# S205C.net
KiCad netlist of a schematic drawn in EAGLE
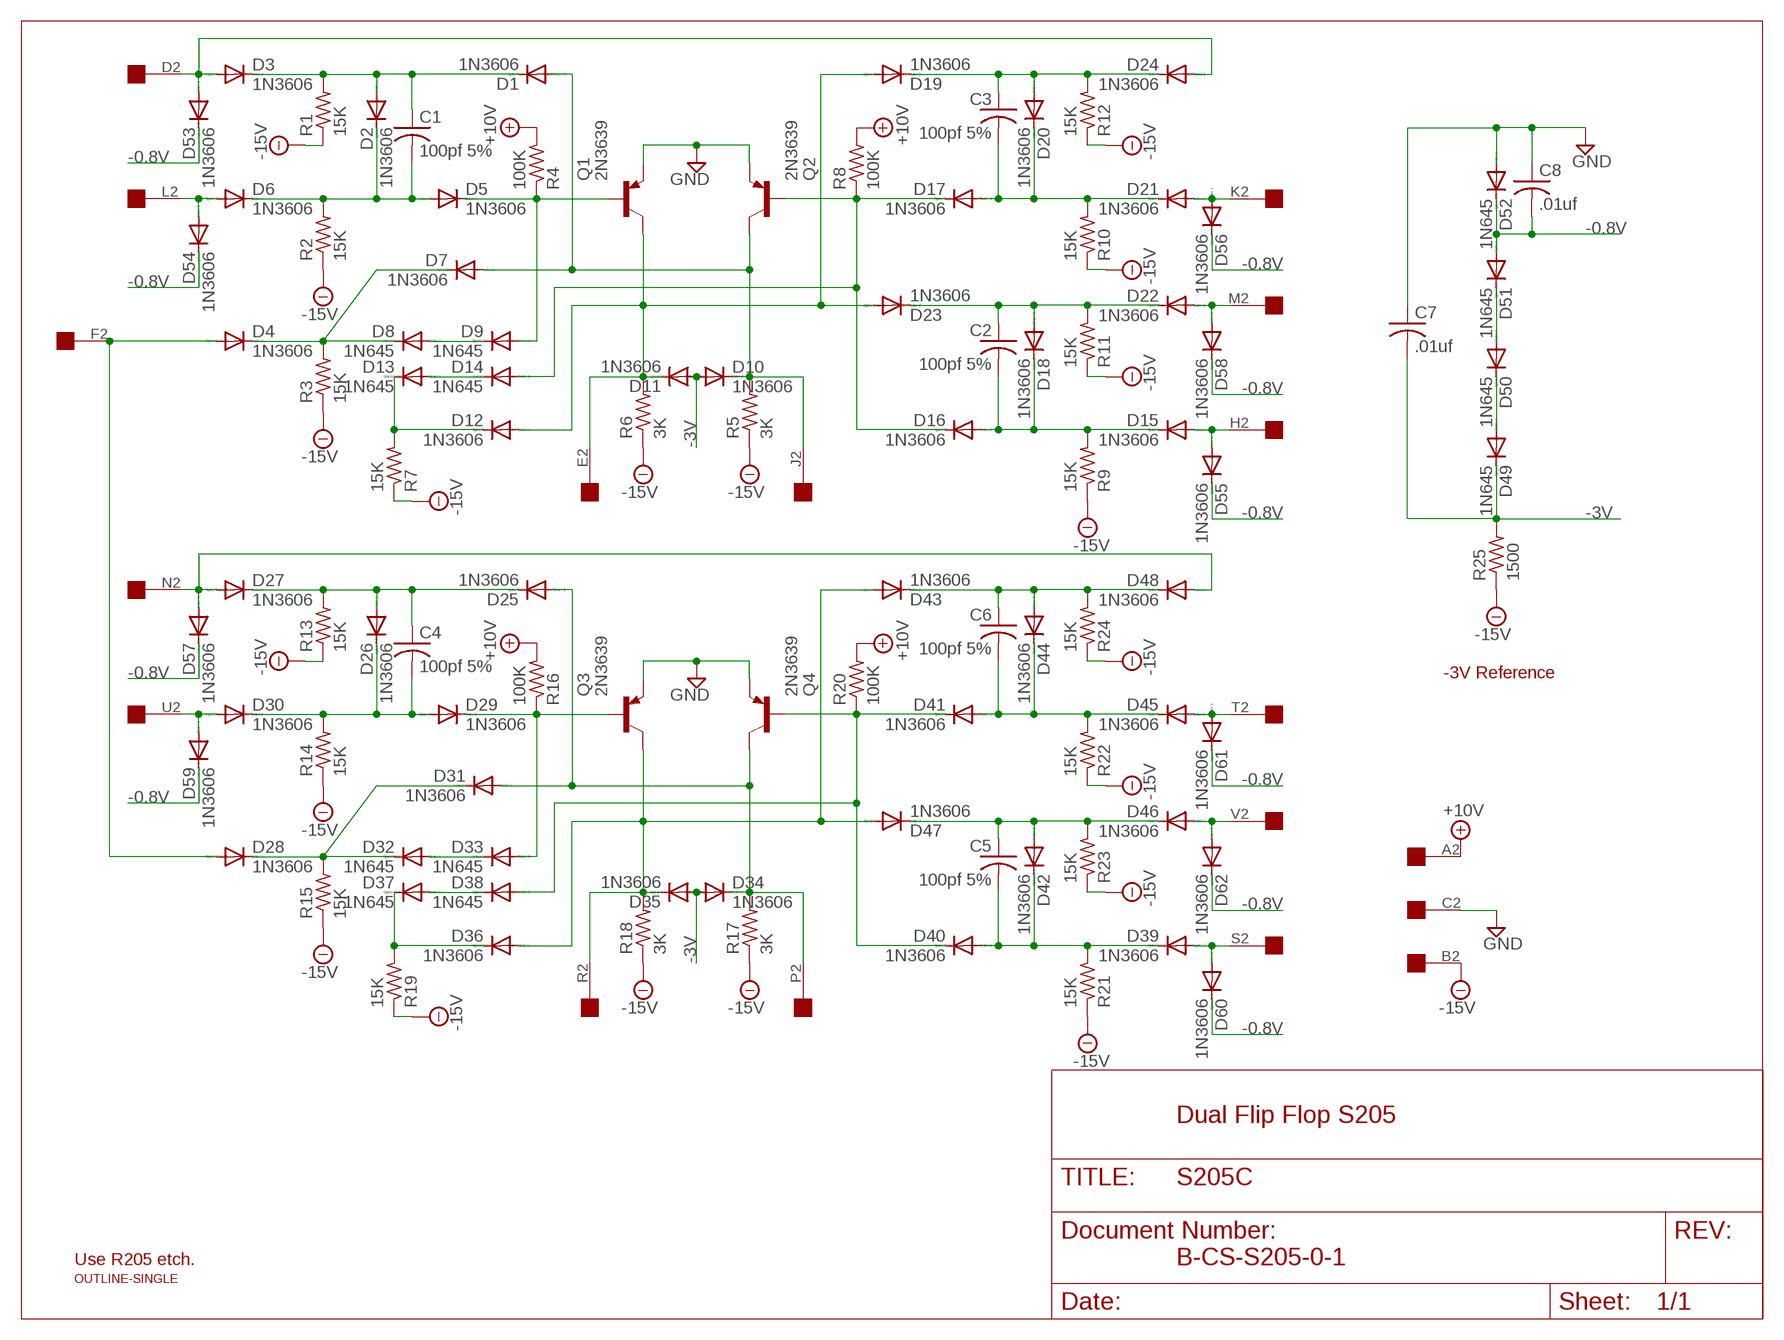
[diagram p0: schematic, sheet 1]

(export (version "E")
  (design (tool "Eeschema 10.0.6"))
  (components
    (comp (ref "C1")
      (value "100pf 5%")
      (footprint "eagle-import:C050-025X075")
      (libsource (lib "eagle-import") (part "C-US050-025X075"))
    )
    (comp (ref "C2")
      (value "100pf 5%")
      (footprint "eagle-import:C050-025X075")
      (libsource (lib "eagle-import") (part "C-US050-025X075"))
    )
    (comp (ref "C3")
      (value "100pf 5%")
      (footprint "eagle-import:C050-025X075")
      (libsource (lib "eagle-import") (part "C-US050-025X075"))
    )
    (comp (ref "C4")
      (value "100pf 5%")
      (footprint "eagle-import:C050-025X075")
      (libsource (lib "eagle-import") (part "C-US050-025X075"))
    )
    (comp (ref "C5")
      (value "100pf 5%")
      (footprint "eagle-import:C050-025X075")
      (libsource (lib "eagle-import") (part "C-US050-025X075"))
    )
    (comp (ref "C6")
      (value "100pf 5%")
      (footprint "eagle-import:C050-025X075")
      (libsource (lib "eagle-import") (part "C-US050-025X075"))
    )
    (comp (ref "C7")
      (value ".01uf")
      (footprint "eagle-import:C050-025X075")
      (libsource (lib "eagle-import") (part "C-US050-025X075"))
    )
    (comp (ref "C8")
      (value ".01uf")
      (footprint "eagle-import:C050-025X075")
      (libsource (lib "eagle-import") (part "C-US050-025X075"))
    )
    (comp (ref "D1")
      (value "1N3606")
      (footprint "eagle-import:DO35-10")
      (libsource (lib "eagle-import") (part "1N4148DO35-10"))
    )
    (comp (ref "D2")
      (value "1N3606")
      (footprint "eagle-import:DO35-10")
      (libsource (lib "eagle-import") (part "1N4148DO35-10"))
    )
    (comp (ref "D3")
      (value "1N3606")
      (footprint "eagle-import:DO35-10")
      (libsource (lib "eagle-import") (part "1N4148DO35-10"))
    )
    (comp (ref "D4")
      (value "1N3606")
      (footprint "eagle-import:DO35-10")
      (libsource (lib "eagle-import") (part "1N4148DO35-10"))
    )
    (comp (ref "D5")
      (value "1N3606")
      (footprint "eagle-import:DO35-10")
      (libsource (lib "eagle-import") (part "1N4148DO35-10"))
    )
    (comp (ref "D6")
      (value "1N3606")
      (footprint "eagle-import:DO35-10")
      (libsource (lib "eagle-import") (part "1N4148DO35-10"))
    )
    (comp (ref "D7")
      (value "1N3606")
      (footprint "eagle-import:DO35-10")
      (libsource (lib "eagle-import") (part "1N4148DO35-10"))
    )
    (comp (ref "D8")
      (value "1N645")
      (footprint "eagle-import:DO35-10")
      (libsource (lib "eagle-import") (part "1N4148DO35-10"))
    )
    (comp (ref "D9")
      (value "1N645")
      (footprint "eagle-import:DO35-10")
      (libsource (lib "eagle-import") (part "1N4148DO35-10"))
    )
    (comp (ref "D10")
      (value "1N3606")
      (footprint "eagle-import:DO35-10")
      (libsource (lib "eagle-import") (part "1N4148DO35-10"))
    )
    (comp (ref "D11")
      (value "1N3606")
      (footprint "eagle-import:DO35-10")
      (libsource (lib "eagle-import") (part "1N4148DO35-10"))
    )
    (comp (ref "D12")
      (value "1N3606")
      (footprint "eagle-import:DO35-10")
      (libsource (lib "eagle-import") (part "1N4148DO35-10"))
    )
    (comp (ref "D13")
      (value "1N645")
      (footprint "eagle-import:DO35-10")
      (libsource (lib "eagle-import") (part "1N4148DO35-10"))
    )
    (comp (ref "D14")
      (value "1N645")
      (footprint "eagle-import:DO35-10")
      (libsource (lib "eagle-import") (part "1N4148DO35-10"))
    )
    (comp (ref "D15")
      (value "1N3606")
      (footprint "eagle-import:DO35-10")
      (libsource (lib "eagle-import") (part "1N4148DO35-10"))
    )
    (comp (ref "D16")
      (value "1N3606")
      (footprint "eagle-import:DO35-10")
      (libsource (lib "eagle-import") (part "1N4148DO35-10"))
    )
    (comp (ref "D17")
      (value "1N3606")
      (footprint "eagle-import:DO35-10")
      (libsource (lib "eagle-import") (part "1N4148DO35-10"))
    )
    (comp (ref "D18")
      (value "1N3606")
      (footprint "eagle-import:DO35-10")
      (libsource (lib "eagle-import") (part "1N4148DO35-10"))
    )
    (comp (ref "D19")
      (value "1N3606")
      (footprint "eagle-import:DO35-10")
      (libsource (lib "eagle-import") (part "1N4148DO35-10"))
    )
    (comp (ref "D20")
      (value "1N3606")
      (footprint "eagle-import:DO35-10")
      (libsource (lib "eagle-import") (part "1N4148DO35-10"))
    )
    (comp (ref "D21")
      (value "1N3606")
      (footprint "eagle-import:DO35-10")
      (libsource (lib "eagle-import") (part "1N4148DO35-10"))
    )
    (comp (ref "D22")
      (value "1N3606")
      (footprint "eagle-import:DO35-10")
      (libsource (lib "eagle-import") (part "1N4148DO35-10"))
    )
    (comp (ref "D23")
      (value "1N3606")
      (footprint "eagle-import:DO35-10")
      (libsource (lib "eagle-import") (part "1N4148DO35-10"))
    )
    (comp (ref "D24")
      (value "1N3606")
      (footprint "eagle-import:DO35-10")
      (libsource (lib "eagle-import") (part "1N4148DO35-10"))
    )
    (comp (ref "D25")
      (value "1N3606")
      (footprint "eagle-import:DO35-10")
      (libsource (lib "eagle-import") (part "1N4148DO35-10"))
    )
    (comp (ref "D26")
      (value "1N3606")
      (footprint "eagle-import:DO35-10")
      (libsource (lib "eagle-import") (part "1N4148DO35-10"))
    )
    (comp (ref "D27")
      (value "1N3606")
      (footprint "eagle-import:DO35-10")
      (libsource (lib "eagle-import") (part "1N4148DO35-10"))
    )
    (comp (ref "D28")
      (value "1N3606")
      (footprint "eagle-import:DO35-10")
      (libsource (lib "eagle-import") (part "1N4148DO35-10"))
    )
    (comp (ref "D29")
      (value "1N3606")
      (footprint "eagle-import:DO35-10")
      (libsource (lib "eagle-import") (part "1N4148DO35-10"))
    )
    (comp (ref "D30")
      (value "1N3606")
      (footprint "eagle-import:DO35-10")
      (libsource (lib "eagle-import") (part "1N4148DO35-10"))
    )
    (comp (ref "D31")
      (value "1N3606")
      (footprint "eagle-import:DO35-10")
      (libsource (lib "eagle-import") (part "1N4148DO35-10"))
    )
    (comp (ref "D32")
      (value "1N645")
      (footprint "eagle-import:DO35-10")
      (libsource (lib "eagle-import") (part "1N4148DO35-10"))
    )
    (comp (ref "D33")
      (value "1N645")
      (footprint "eagle-import:DO35-10")
      (libsource (lib "eagle-import") (part "1N4148DO35-10"))
    )
    (comp (ref "D34")
      (value "1N3606")
      (footprint "eagle-import:DO35-10")
      (libsource (lib "eagle-import") (part "1N4148DO35-10"))
    )
    (comp (ref "D35")
      (value "1N3606")
      (footprint "eagle-import:DO35-10")
      (libsource (lib "eagle-import") (part "1N4148DO35-10"))
    )
    (comp (ref "D36")
      (value "1N3606")
      (footprint "eagle-import:DO35-10")
      (libsource (lib "eagle-import") (part "1N4148DO35-10"))
    )
    (comp (ref "D37")
      (value "1N645")
      (footprint "eagle-import:DO35-10")
      (libsource (lib "eagle-import") (part "1N4148DO35-10"))
    )
    (comp (ref "D38")
      (value "1N645")
      (footprint "eagle-import:DO35-10")
      (libsource (lib "eagle-import") (part "1N4148DO35-10"))
    )
    (comp (ref "D39")
      (value "1N3606")
      (footprint "eagle-import:DO35-10")
      (libsource (lib "eagle-import") (part "1N4148DO35-10"))
    )
    (comp (ref "D40")
      (value "1N3606")
      (footprint "eagle-import:DO35-10")
      (libsource (lib "eagle-import") (part "1N4148DO35-10"))
    )
    (comp (ref "D41")
      (value "1N3606")
      (footprint "eagle-import:DO35-10")
      (libsource (lib "eagle-import") (part "1N4148DO35-10"))
    )
    (comp (ref "D42")
      (value "1N3606")
      (footprint "eagle-import:DO35-10")
      (libsource (lib "eagle-import") (part "1N4148DO35-10"))
    )
    (comp (ref "D43")
      (value "1N3606")
      (footprint "eagle-import:DO35-10")
      (libsource (lib "eagle-import") (part "1N4148DO35-10"))
    )
    (comp (ref "D44")
      (value "1N3606")
      (footprint "eagle-import:DO35-10")
      (libsource (lib "eagle-import") (part "1N4148DO35-10"))
    )
    (comp (ref "D45")
      (value "1N3606")
      (footprint "eagle-import:DO35-10")
      (libsource (lib "eagle-import") (part "1N4148DO35-10"))
    )
    (comp (ref "D46")
      (value "1N3606")
      (footprint "eagle-import:DO35-10")
      (libsource (lib "eagle-import") (part "1N4148DO35-10"))
    )
    (comp (ref "D47")
      (value "1N3606")
      (footprint "eagle-import:DO35-10")
      (libsource (lib "eagle-import") (part "1N4148DO35-10"))
    )
    (comp (ref "D48")
      (value "1N3606")
      (footprint "eagle-import:DO35-10")
      (libsource (lib "eagle-import") (part "1N4148DO35-10"))
    )
    (comp (ref "D49")
      (value "1N645")
      (footprint "eagle-import:DO35-10")
      (libsource (lib "eagle-import") (part "1N4148DO35-10"))
    )
    (comp (ref "D50")
      (value "1N645")
      (footprint "eagle-import:DO35-10")
      (libsource (lib "eagle-import") (part "1N4148DO35-10"))
    )
    (comp (ref "D51")
      (value "1N645")
      (footprint "eagle-import:DO35-10")
      (libsource (lib "eagle-import") (part "1N4148DO35-10"))
    )
    (comp (ref "D52")
      (value "1N645")
      (footprint "eagle-import:DO35-10")
      (libsource (lib "eagle-import") (part "1N4148DO35-10"))
    )
    (comp (ref "D53")
      (value "1N3606")
      (footprint "eagle-import:DO35-10")
      (libsource (lib "eagle-import") (part "1N4148DO35-10"))
    )
    (comp (ref "D54")
      (value "1N3606")
      (footprint "eagle-import:DO35-10")
      (libsource (lib "eagle-import") (part "1N4148DO35-10"))
    )
    (comp (ref "D55")
      (value "1N3606")
      (footprint "eagle-import:DO35-10")
      (libsource (lib "eagle-import") (part "1N4148DO35-10"))
    )
    (comp (ref "D56")
      (value "1N3606")
      (footprint "eagle-import:DO35-10")
      (libsource (lib "eagle-import") (part "1N4148DO35-10"))
    )
    (comp (ref "D57")
      (value "1N3606")
      (footprint "eagle-import:DO35-10")
      (libsource (lib "eagle-import") (part "1N4148DO35-10"))
    )
    (comp (ref "D58")
      (value "1N3606")
      (footprint "eagle-import:DO35-10")
      (libsource (lib "eagle-import") (part "1N4148DO35-10"))
    )
    (comp (ref "D59")
      (value "1N3606")
      (footprint "eagle-import:DO35-10")
      (libsource (lib "eagle-import") (part "1N4148DO35-10"))
    )
    (comp (ref "D60")
      (value "1N3606")
      (footprint "eagle-import:DO35-10")
      (libsource (lib "eagle-import") (part "1N4148DO35-10"))
    )
    (comp (ref "D61")
      (value "1N3606")
      (footprint "eagle-import:DO35-10")
      (libsource (lib "eagle-import") (part "1N4148DO35-10"))
    )
    (comp (ref "D62")
      (value "1N3606")
      (footprint "eagle-import:DO35-10")
      (libsource (lib "eagle-import") (part "1N4148DO35-10"))
    )
    (comp (ref "Q1")
      (value "2N3639")
      (footprint "eagle-import:TO39")
      (libsource (lib "eagle-import") (part "2N3637"))
    )
    (comp (ref "Q2")
      (value "2N3639")
      (footprint "eagle-import:TO39")
      (libsource (lib "eagle-import") (part "2N3637"))
    )
    (comp (ref "Q3")
      (value "2N3639")
      (footprint "eagle-import:TO39")
      (libsource (lib "eagle-import") (part "2N3637"))
    )
    (comp (ref "Q4")
      (value "2N3639")
      (footprint "eagle-import:TO39")
      (libsource (lib "eagle-import") (part "2N3637"))
    )
    (comp (ref "R1")
      (value "15K")
      (footprint "eagle-import:0207_10")
      (libsource (lib "eagle-import") (part "R-US_0207/10"))
    )
    (comp (ref "R2")
      (value "15K")
      (footprint "eagle-import:0207_10")
      (libsource (lib "eagle-import") (part "R-US_0207/10"))
    )
    (comp (ref "R3")
      (value "15K")
      (footprint "eagle-import:0207_10")
      (libsource (lib "eagle-import") (part "R-US_0207/10"))
    )
    (comp (ref "R4")
      (value "100K")
      (footprint "eagle-import:0207_10")
      (libsource (lib "eagle-import") (part "R-US_0207/10"))
    )
    (comp (ref "R5")
      (value "3K")
      (footprint "eagle-import:0207_10")
      (libsource (lib "eagle-import") (part "R-US_0207/10"))
    )
    (comp (ref "R6")
      (value "3K")
      (footprint "eagle-import:0207_10")
      (libsource (lib "eagle-import") (part "R-US_0207/10"))
    )
    (comp (ref "R7")
      (value "15K")
      (footprint "eagle-import:0207_10")
      (libsource (lib "eagle-import") (part "R-US_0207/10"))
    )
    (comp (ref "R8")
      (value "100K")
      (footprint "eagle-import:0207_10")
      (libsource (lib "eagle-import") (part "R-US_0207/10"))
    )
    (comp (ref "R9")
      (value "15K")
      (footprint "eagle-import:0207_10")
      (libsource (lib "eagle-import") (part "R-US_0207/10"))
    )
    (comp (ref "R10")
      (value "15K")
      (footprint "eagle-import:0207_10")
      (libsource (lib "eagle-import") (part "R-US_0207/10"))
    )
    (comp (ref "R11")
      (value "15K")
      (footprint "eagle-import:0207_10")
      (libsource (lib "eagle-import") (part "R-US_0207/10"))
    )
    (comp (ref "R12")
      (value "15K")
      (footprint "eagle-import:0207_10")
      (libsource (lib "eagle-import") (part "R-US_0207/10"))
    )
    (comp (ref "R13")
      (value "15K")
      (footprint "eagle-import:0207_10")
      (libsource (lib "eagle-import") (part "R-US_0207/10"))
    )
    (comp (ref "R14")
      (value "15K")
      (footprint "eagle-import:0207_10")
      (libsource (lib "eagle-import") (part "R-US_0207/10"))
    )
    (comp (ref "R15")
      (value "15K")
      (footprint "eagle-import:0207_10")
      (libsource (lib "eagle-import") (part "R-US_0207/10"))
    )
    (comp (ref "R16")
      (value "100K")
      (footprint "eagle-import:0207_10")
      (libsource (lib "eagle-import") (part "R-US_0207/10"))
    )
    (comp (ref "R17")
      (value "3K")
      (footprint "eagle-import:0207_10")
      (libsource (lib "eagle-import") (part "R-US_0207/10"))
    )
    (comp (ref "R18")
      (value "3K")
      (footprint "eagle-import:0207_10")
      (libsource (lib "eagle-import") (part "R-US_0207/10"))
    )
    (comp (ref "R19")
      (value "15K")
      (footprint "eagle-import:0207_10")
      (libsource (lib "eagle-import") (part "R-US_0207/10"))
    )
    (comp (ref "R20")
      (value "100K")
      (footprint "eagle-import:0207_10")
      (libsource (lib "eagle-import") (part "R-US_0207/10"))
    )
    (comp (ref "R21")
      (value "15K")
      (footprint "eagle-import:0207_10")
      (libsource (lib "eagle-import") (part "R-US_0207/10"))
    )
    (comp (ref "R22")
      (value "15K")
      (footprint "eagle-import:0207_10")
      (libsource (lib "eagle-import") (part "R-US_0207/10"))
    )
    (comp (ref "R23")
      (value "15K")
      (footprint "eagle-import:0207_10")
      (libsource (lib "eagle-import") (part "R-US_0207/10"))
    )
    (comp (ref "R24")
      (value "15K")
      (footprint "eagle-import:0207_10")
      (libsource (lib "eagle-import") (part "R-US_0207/10"))
    )
    (comp (ref "R25")
      (value "1500")
      (footprint "eagle-import:0207_10")
      (libsource (lib "eagle-import") (part "R-US_0207/10"))
    )
    (comp (ref "U$1")
      (value "OUTLINE-SINGLE")
      (footprint "eagle-import:SINGLE")
      (libsource (lib "eagle-import") (part "OUTLINE-SINGLE"))
    )
    (comp (ref "U$2")
      (value "EDGE-1")
      (footprint "eagle-import:EDGE-CON1")
      (libsource (lib "eagle-import") (part "EDGE-1"))
    )
  )
  (nets
    (net (code "1") (name "+10V") (class "Default")
      (node (ref "R16") (pin "2") (pinfunction "2_2") (pintype "passive"))
      (node (ref "R20") (pin "2") (pinfunction "2_2") (pintype "passive"))
      (node (ref "R4") (pin "2") (pinfunction "2_2") (pintype "passive"))
      (node (ref "R8") (pin "2") (pinfunction "2_2") (pintype "passive"))
      (node (ref "U$2") (pin "A2") (pinfunction "1_A2") (pintype "bidirectional"))
    )
    (net (code "2") (name "-15V") (class "Default")
      (node (ref "R1") (pin "1") (pinfunction "1_1") (pintype "passive"))
      (node (ref "R10") (pin "1") (pinfunction "1_1") (pintype "passive"))
      (node (ref "R11") (pin "1") (pinfunction "1_1") (pintype "passive"))
      (node (ref "R12") (pin "1") (pinfunction "1_1") (pintype "passive"))
      (node (ref "R13") (pin "1") (pinfunction "1_1") (pintype "passive"))
      (node (ref "R14") (pin "1") (pinfunction "1_1") (pintype "passive"))
      (node (ref "R15") (pin "1") (pinfunction "1_1") (pintype "passive"))
      (node (ref "R17") (pin "1") (pinfunction "1_1") (pintype "passive"))
      (node (ref "R18") (pin "1") (pinfunction "1_1") (pintype "passive"))
      (node (ref "R19") (pin "1") (pinfunction "1_1") (pintype "passive"))
      (node (ref "R2") (pin "1") (pinfunction "1_1") (pintype "passive"))
      (node (ref "R21") (pin "1") (pinfunction "1_1") (pintype "passive"))
      (node (ref "R22") (pin "1") (pinfunction "1_1") (pintype "passive"))
      (node (ref "R23") (pin "1") (pinfunction "1_1") (pintype "passive"))
      (node (ref "R24") (pin "1") (pinfunction "1_1") (pintype "passive"))
      (node (ref "R25") (pin "1") (pinfunction "1_1") (pintype "passive"))
      (node (ref "R3") (pin "1") (pinfunction "1_1") (pintype "passive"))
      (node (ref "R5") (pin "1") (pinfunction "1_1") (pintype "passive"))
      (node (ref "R6") (pin "1") (pinfunction "1_1") (pintype "passive"))
      (node (ref "R7") (pin "1") (pinfunction "1_1") (pintype "passive"))
      (node (ref "R9") (pin "1") (pinfunction "1_1") (pintype "passive"))
      (node (ref "U$2") (pin "B2") (pinfunction "1_B2") (pintype "bidirectional"))
    )
    (net (code "3") (name "/-0.8V") (class "Default")
      (node (ref "C8") (pin "2") (pinfunction "2_2") (pintype "passive"))
      (node (ref "D51") (pin "A") (pinfunction "A_A") (pintype "passive"))
      (node (ref "D52") (pin "C") (pinfunction "C_C") (pintype "passive"))
      (node (ref "D53") (pin "C") (pinfunction "C_C") (pintype "passive"))
      (node (ref "D54") (pin "C") (pinfunction "C_C") (pintype "passive"))
      (node (ref "D55") (pin "C") (pinfunction "C_C") (pintype "passive"))
      (node (ref "D56") (pin "C") (pinfunction "C_C") (pintype "passive"))
      (node (ref "D57") (pin "C") (pinfunction "C_C") (pintype "passive"))
      (node (ref "D58") (pin "C") (pinfunction "C_C") (pintype "passive"))
      (node (ref "D59") (pin "C") (pinfunction "C_C") (pintype "passive"))
      (node (ref "D60") (pin "C") (pinfunction "C_C") (pintype "passive"))
      (node (ref "D61") (pin "C") (pinfunction "C_C") (pintype "passive"))
      (node (ref "D62") (pin "C") (pinfunction "C_C") (pintype "passive"))
    )
    (net (code "4") (name "/-3V") (class "Default")
      (node (ref "C7") (pin "2") (pinfunction "2_2") (pintype "passive"))
      (node (ref "D10") (pin "A") (pinfunction "A_A") (pintype "passive"))
      (node (ref "D11") (pin "A") (pinfunction "A_A") (pintype "passive"))
      (node (ref "D34") (pin "A") (pinfunction "A_A") (pintype "passive"))
      (node (ref "D35") (pin "A") (pinfunction "A_A") (pintype "passive"))
      (node (ref "D49") (pin "C") (pinfunction "C_C") (pintype "passive"))
      (node (ref "R25") (pin "2") (pinfunction "2_2") (pintype "passive"))
    )
    (net (code "5") (name "GND") (class "Default")
      (node (ref "C7") (pin "1") (pinfunction "1_1") (pintype "passive"))
      (node (ref "C8") (pin "1") (pinfunction "1_1") (pintype "passive"))
      (node (ref "D52") (pin "A") (pinfunction "A_A") (pintype "passive"))
      (node (ref "Q1") (pin "1") (pinfunction "E_1") (pintype "passive"))
      (node (ref "Q2") (pin "1") (pinfunction "E_1") (pintype "passive"))
      (node (ref "Q3") (pin "1") (pinfunction "E_1") (pintype "passive"))
      (node (ref "Q4") (pin "1") (pinfunction "E_1") (pintype "passive"))
      (node (ref "U$2") (pin "C2") (pinfunction "1_C2") (pintype "bidirectional"))
    )
    (net (code "6") (name "Net-(C1-Pad1)") (class "Default")
      (node (ref "C1") (pin "1") (pinfunction "1_1") (pintype "passive"))
      (node (ref "D1") (pin "C") (pinfunction "C_C") (pintype "passive"))
      (node (ref "D2") (pin "A") (pinfunction "A_A") (pintype "passive"))
      (node (ref "D3") (pin "C") (pinfunction "C_C") (pintype "passive"))
      (node (ref "R1") (pin "2") (pinfunction "2_2") (pintype "passive"))
    )
    (net (code "7") (name "Net-(C1-Pad2)") (class "Default")
      (node (ref "C1") (pin "2") (pinfunction "2_2") (pintype "passive"))
      (node (ref "D2") (pin "C") (pinfunction "C_C") (pintype "passive"))
      (node (ref "D5") (pin "A") (pinfunction "A_A") (pintype "passive"))
      (node (ref "D6") (pin "C") (pinfunction "C_C") (pintype "passive"))
      (node (ref "R2") (pin "2") (pinfunction "2_2") (pintype "passive"))
    )
    (net (code "8") (name "Net-(C2-Pad1)") (class "Default")
      (node (ref "C2") (pin "1") (pinfunction "1_1") (pintype "passive"))
      (node (ref "D18") (pin "A") (pinfunction "A_A") (pintype "passive"))
      (node (ref "D22") (pin "C") (pinfunction "C_C") (pintype "passive"))
      (node (ref "D23") (pin "C") (pinfunction "C_C") (pintype "passive"))
      (node (ref "R11") (pin "2") (pinfunction "2_2") (pintype "passive"))
    )
    (net (code "9") (name "Net-(C2-Pad2)") (class "Default")
      (node (ref "C2") (pin "2") (pinfunction "2_2") (pintype "passive"))
      (node (ref "D15") (pin "C") (pinfunction "C_C") (pintype "passive"))
      (node (ref "D16") (pin "A") (pinfunction "A_A") (pintype "passive"))
      (node (ref "D18") (pin "C") (pinfunction "C_C") (pintype "passive"))
      (node (ref "R9") (pin "2") (pinfunction "2_2") (pintype "passive"))
    )
    (net (code "10") (name "Net-(C3-Pad1)") (class "Default")
      (node (ref "C3") (pin "1") (pinfunction "1_1") (pintype "passive"))
      (node (ref "D19") (pin "C") (pinfunction "C_C") (pintype "passive"))
      (node (ref "D20") (pin "A") (pinfunction "A_A") (pintype "passive"))
      (node (ref "D24") (pin "C") (pinfunction "C_C") (pintype "passive"))
      (node (ref "R12") (pin "2") (pinfunction "2_2") (pintype "passive"))
    )
    (net (code "11") (name "Net-(C3-Pad2)") (class "Default")
      (node (ref "C3") (pin "2") (pinfunction "2_2") (pintype "passive"))
      (node (ref "D17") (pin "A") (pinfunction "A_A") (pintype "passive"))
      (node (ref "D20") (pin "C") (pinfunction "C_C") (pintype "passive"))
      (node (ref "D21") (pin "C") (pinfunction "C_C") (pintype "passive"))
      (node (ref "R10") (pin "2") (pinfunction "2_2") (pintype "passive"))
    )
    (net (code "12") (name "Net-(C4-Pad1)") (class "Default")
      (node (ref "C4") (pin "1") (pinfunction "1_1") (pintype "passive"))
      (node (ref "D25") (pin "C") (pinfunction "C_C") (pintype "passive"))
      (node (ref "D26") (pin "A") (pinfunction "A_A") (pintype "passive"))
      (node (ref "D27") (pin "C") (pinfunction "C_C") (pintype "passive"))
      (node (ref "R13") (pin "2") (pinfunction "2_2") (pintype "passive"))
    )
    (net (code "13") (name "Net-(C4-Pad2)") (class "Default")
      (node (ref "C4") (pin "2") (pinfunction "2_2") (pintype "passive"))
      (node (ref "D26") (pin "C") (pinfunction "C_C") (pintype "passive"))
      (node (ref "D29") (pin "A") (pinfunction "A_A") (pintype "passive"))
      (node (ref "D30") (pin "C") (pinfunction "C_C") (pintype "passive"))
      (node (ref "R14") (pin "2") (pinfunction "2_2") (pintype "passive"))
    )
    (net (code "14") (name "Net-(C5-Pad1)") (class "Default")
      (node (ref "C5") (pin "1") (pinfunction "1_1") (pintype "passive"))
      (node (ref "D42") (pin "A") (pinfunction "A_A") (pintype "passive"))
      (node (ref "D46") (pin "C") (pinfunction "C_C") (pintype "passive"))
      (node (ref "D47") (pin "C") (pinfunction "C_C") (pintype "passive"))
      (node (ref "R23") (pin "2") (pinfunction "2_2") (pintype "passive"))
    )
    (net (code "15") (name "Net-(C5-Pad2)") (class "Default")
      (node (ref "C5") (pin "2") (pinfunction "2_2") (pintype "passive"))
      (node (ref "D39") (pin "C") (pinfunction "C_C") (pintype "passive"))
      (node (ref "D40") (pin "A") (pinfunction "A_A") (pintype "passive"))
      (node (ref "D42") (pin "C") (pinfunction "C_C") (pintype "passive"))
      (node (ref "R21") (pin "2") (pinfunction "2_2") (pintype "passive"))
    )
    (net (code "16") (name "Net-(C6-Pad1)") (class "Default")
      (node (ref "C6") (pin "1") (pinfunction "1_1") (pintype "passive"))
      (node (ref "D43") (pin "C") (pinfunction "C_C") (pintype "passive"))
      (node (ref "D44") (pin "A") (pinfunction "A_A") (pintype "passive"))
      (node (ref "D48") (pin "C") (pinfunction "C_C") (pintype "passive"))
      (node (ref "R24") (pin "2") (pinfunction "2_2") (pintype "passive"))
    )
    (net (code "17") (name "Net-(C6-Pad2)") (class "Default")
      (node (ref "C6") (pin "2") (pinfunction "2_2") (pintype "passive"))
      (node (ref "D41") (pin "A") (pinfunction "A_A") (pintype "passive"))
      (node (ref "D44") (pin "C") (pinfunction "C_C") (pintype "passive"))
      (node (ref "D45") (pin "C") (pinfunction "C_C") (pintype "passive"))
      (node (ref "R22") (pin "2") (pinfunction "2_2") (pintype "passive"))
    )
    (net (code "18") (name "Net-(D4-PadC)") (class "Default")
      (node (ref "D4") (pin "C") (pinfunction "C_C") (pintype "passive"))
      (node (ref "D7") (pin "C") (pinfunction "C_C") (pintype "passive"))
      (node (ref "D8") (pin "C") (pinfunction "C_C") (pintype "passive"))
      (node (ref "R3") (pin "2") (pinfunction "2_2") (pintype "passive"))
    )
    (net (code "19") (name "Net-(D8-PadA)") (class "Default")
      (node (ref "D8") (pin "A") (pinfunction "A_A") (pintype "passive"))
      (node (ref "D9") (pin "C") (pinfunction "C_C") (pintype "passive"))
    )
    (net (code "20") (name "Net-(D12-PadC)") (class "Default")
      (node (ref "D12") (pin "C") (pinfunction "C_C") (pintype "passive"))
      (node (ref "D13") (pin "C") (pinfunction "C_C") (pintype "passive"))
      (node (ref "R7") (pin "2") (pinfunction "2_2") (pintype "passive"))
    )
    (net (code "21") (name "Net-(D13-PadA)") (class "Default")
      (node (ref "D13") (pin "A") (pinfunction "A_A") (pintype "passive"))
      (node (ref "D14") (pin "C") (pinfunction "C_C") (pintype "passive"))
    )
    (net (code "22") (name "Net-(D28-PadC)") (class "Default")
      (node (ref "D28") (pin "C") (pinfunction "C_C") (pintype "passive"))
      (node (ref "D31") (pin "C") (pinfunction "C_C") (pintype "passive"))
      (node (ref "D32") (pin "C") (pinfunction "C_C") (pintype "passive"))
      (node (ref "R15") (pin "2") (pinfunction "2_2") (pintype "passive"))
    )
    (net (code "23") (name "Net-(D32-PadA)") (class "Default")
      (node (ref "D32") (pin "A") (pinfunction "A_A") (pintype "passive"))
      (node (ref "D33") (pin "C") (pinfunction "C_C") (pintype "passive"))
    )
    (net (code "24") (name "Net-(D36-PadC)") (class "Default")
      (node (ref "D36") (pin "C") (pinfunction "C_C") (pintype "passive"))
      (node (ref "D37") (pin "C") (pinfunction "C_C") (pintype "passive"))
      (node (ref "R19") (pin "2") (pinfunction "2_2") (pintype "passive"))
    )
    (net (code "25") (name "Net-(D37-PadA)") (class "Default")
      (node (ref "D37") (pin "A") (pinfunction "A_A") (pintype "passive"))
      (node (ref "D38") (pin "C") (pinfunction "C_C") (pintype "passive"))
    )
    (net (code "26") (name "Net-(D49-PadA)") (class "Default")
      (node (ref "D49") (pin "A") (pinfunction "A_A") (pintype "passive"))
      (node (ref "D50") (pin "C") (pinfunction "C_C") (pintype "passive"))
    )
    (net (code "27") (name "Net-(D50-PadA)") (class "Default")
      (node (ref "D50") (pin "A") (pinfunction "A_A") (pintype "passive"))
      (node (ref "D51") (pin "C") (pinfunction "C_C") (pintype "passive"))
    )
    (net (code "28") (name "Net-(Q1-B)") (class "Default")
      (node (ref "D5") (pin "C") (pinfunction "C_C") (pintype "passive"))
      (node (ref "D9") (pin "A") (pinfunction "A_A") (pintype "passive"))
      (node (ref "Q1") (pin "2") (pinfunction "B_2") (pintype "passive"))
      (node (ref "R4") (pin "1") (pinfunction "1_1") (pintype "passive"))
    )
    (net (code "29") (name "Net-(Q1-C)") (class "Default")
      (node (ref "D11") (pin "C") (pinfunction "C_C") (pintype "passive"))
      (node (ref "D12") (pin "A") (pinfunction "A_A") (pintype "passive"))
      (node (ref "D19") (pin "A") (pinfunction "A_A") (pintype "passive"))
      (node (ref "D23") (pin "A") (pinfunction "A_A") (pintype "passive"))
      (node (ref "Q1") (pin "3") (pinfunction "C_3") (pintype "passive"))
      (node (ref "R6") (pin "2") (pinfunction "2_2") (pintype "passive"))
      (node (ref "U$2") (pin "E2") (pinfunction "1_E2") (pintype "bidirectional"))
    )
    (net (code "30") (name "Net-(Q2-B)") (class "Default")
      (node (ref "D14") (pin "A") (pinfunction "A_A") (pintype "passive"))
      (node (ref "D16") (pin "C") (pinfunction "C_C") (pintype "passive"))
      (node (ref "D17") (pin "C") (pinfunction "C_C") (pintype "passive"))
      (node (ref "Q2") (pin "2") (pinfunction "B_2") (pintype "passive"))
      (node (ref "R8") (pin "1") (pinfunction "1_1") (pintype "passive"))
    )
    (net (code "31") (name "Net-(Q2-C)") (class "Default")
      (node (ref "D1") (pin "A") (pinfunction "A_A") (pintype "passive"))
      (node (ref "D10") (pin "C") (pinfunction "C_C") (pintype "passive"))
      (node (ref "D7") (pin "A") (pinfunction "A_A") (pintype "passive"))
      (node (ref "Q2") (pin "3") (pinfunction "C_3") (pintype "passive"))
      (node (ref "R5") (pin "2") (pinfunction "2_2") (pintype "passive"))
      (node (ref "U$2") (pin "J2") (pinfunction "1_J2") (pintype "bidirectional"))
    )
    (net (code "32") (name "Net-(Q3-B)") (class "Default")
      (node (ref "D29") (pin "C") (pinfunction "C_C") (pintype "passive"))
      (node (ref "D33") (pin "A") (pinfunction "A_A") (pintype "passive"))
      (node (ref "Q3") (pin "2") (pinfunction "B_2") (pintype "passive"))
      (node (ref "R16") (pin "1") (pinfunction "1_1") (pintype "passive"))
    )
    (net (code "33") (name "Net-(Q3-C)") (class "Default")
      (node (ref "D35") (pin "C") (pinfunction "C_C") (pintype "passive"))
      (node (ref "D36") (pin "A") (pinfunction "A_A") (pintype "passive"))
      (node (ref "D43") (pin "A") (pinfunction "A_A") (pintype "passive"))
      (node (ref "D47") (pin "A") (pinfunction "A_A") (pintype "passive"))
      (node (ref "Q3") (pin "3") (pinfunction "C_3") (pintype "passive"))
      (node (ref "R18") (pin "2") (pinfunction "2_2") (pintype "passive"))
      (node (ref "U$2") (pin "R2") (pinfunction "1_R2") (pintype "bidirectional"))
    )
    (net (code "34") (name "Net-(Q4-B)") (class "Default")
      (node (ref "D38") (pin "A") (pinfunction "A_A") (pintype "passive"))
      (node (ref "D40") (pin "C") (pinfunction "C_C") (pintype "passive"))
      (node (ref "D41") (pin "C") (pinfunction "C_C") (pintype "passive"))
      (node (ref "Q4") (pin "2") (pinfunction "B_2") (pintype "passive"))
      (node (ref "R20") (pin "1") (pinfunction "1_1") (pintype "passive"))
    )
    (net (code "35") (name "Net-(Q4-C)") (class "Default")
      (node (ref "D25") (pin "A") (pinfunction "A_A") (pintype "passive"))
      (node (ref "D31") (pin "A") (pinfunction "A_A") (pintype "passive"))
      (node (ref "D34") (pin "C") (pinfunction "C_C") (pintype "passive"))
      (node (ref "Q4") (pin "3") (pinfunction "C_3") (pintype "passive"))
      (node (ref "R17") (pin "2") (pinfunction "2_2") (pintype "passive"))
      (node (ref "U$2") (pin "P2") (pinfunction "1_P2") (pintype "bidirectional"))
    )
    (net (code "36") (name "Net-(U$2D-1)") (class "Default")
      (node (ref "D24") (pin "A") (pinfunction "A_A") (pintype "passive"))
      (node (ref "D3") (pin "A") (pinfunction "A_A") (pintype "passive"))
      (node (ref "D53") (pin "A") (pinfunction "A_A") (pintype "passive"))
      (node (ref "U$2") (pin "D2") (pinfunction "1_D2") (pintype "bidirectional"))
    )
    (net (code "37") (name "Net-(U$2F-1)") (class "Default")
      (node (ref "D28") (pin "A") (pinfunction "A_A") (pintype "passive"))
      (node (ref "D4") (pin "A") (pinfunction "A_A") (pintype "passive"))
      (node (ref "U$2") (pin "F2") (pinfunction "1_F2") (pintype "bidirectional"))
    )
    (net (code "38") (name "Net-(U$2G-1)") (class "Default")
      (node (ref "D15") (pin "A") (pinfunction "A_A") (pintype "passive"))
      (node (ref "D55") (pin "A") (pinfunction "A_A") (pintype "passive"))
      (node (ref "U$2") (pin "H2") (pinfunction "1_H2") (pintype "bidirectional"))
    )
    (net (code "39") (name "Net-(U$2I-1)") (class "Default")
      (node (ref "D21") (pin "A") (pinfunction "A_A") (pintype "passive"))
      (node (ref "D56") (pin "A") (pinfunction "A_A") (pintype "passive"))
      (node (ref "U$2") (pin "K2") (pinfunction "1_K2") (pintype "bidirectional"))
    )
    (net (code "40") (name "Net-(U$2J-1)") (class "Default")
      (node (ref "D54") (pin "A") (pinfunction "A_A") (pintype "passive"))
      (node (ref "D6") (pin "A") (pinfunction "A_A") (pintype "passive"))
      (node (ref "U$2") (pin "L2") (pinfunction "1_L2") (pintype "bidirectional"))
    )
    (net (code "41") (name "Net-(U$2K-1)") (class "Default")
      (node (ref "D22") (pin "A") (pinfunction "A_A") (pintype "passive"))
      (node (ref "D58") (pin "A") (pinfunction "A_A") (pintype "passive"))
      (node (ref "U$2") (pin "M2") (pinfunction "1_M2") (pintype "bidirectional"))
    )
    (net (code "42") (name "Net-(U$2L-1)") (class "Default")
      (node (ref "D27") (pin "A") (pinfunction "A_A") (pintype "passive"))
      (node (ref "D48") (pin "A") (pinfunction "A_A") (pintype "passive"))
      (node (ref "D57") (pin "A") (pinfunction "A_A") (pintype "passive"))
      (node (ref "U$2") (pin "N2") (pinfunction "1_N2") (pintype "bidirectional"))
    )
    (net (code "43") (name "Net-(U$2O-1)") (class "Default")
      (node (ref "D39") (pin "A") (pinfunction "A_A") (pintype "passive"))
      (node (ref "D60") (pin "A") (pinfunction "A_A") (pintype "passive"))
      (node (ref "U$2") (pin "S2") (pinfunction "1_S2") (pintype "bidirectional"))
    )
    (net (code "44") (name "Net-(U$2P-1)") (class "Default")
      (node (ref "D45") (pin "A") (pinfunction "A_A") (pintype "passive"))
      (node (ref "D61") (pin "A") (pinfunction "A_A") (pintype "passive"))
      (node (ref "U$2") (pin "T2") (pinfunction "1_T2") (pintype "bidirectional"))
    )
    (net (code "45") (name "Net-(U$2Q-1)") (class "Default")
      (node (ref "D30") (pin "A") (pinfunction "A_A") (pintype "passive"))
      (node (ref "D59") (pin "A") (pinfunction "A_A") (pintype "passive"))
      (node (ref "U$2") (pin "U2") (pinfunction "1_U2") (pintype "bidirectional"))
    )
    (net (code "46") (name "Net-(U$2R-1)") (class "Default")
      (node (ref "D46") (pin "A") (pinfunction "A_A") (pintype "passive"))
      (node (ref "D62") (pin "A") (pinfunction "A_A") (pintype "passive"))
      (node (ref "U$2") (pin "V2") (pinfunction "1_V2") (pintype "bidirectional"))
    )
  )
)
